# RP2040.net
KiCad netlist of a schematic drawn in Altium Designer
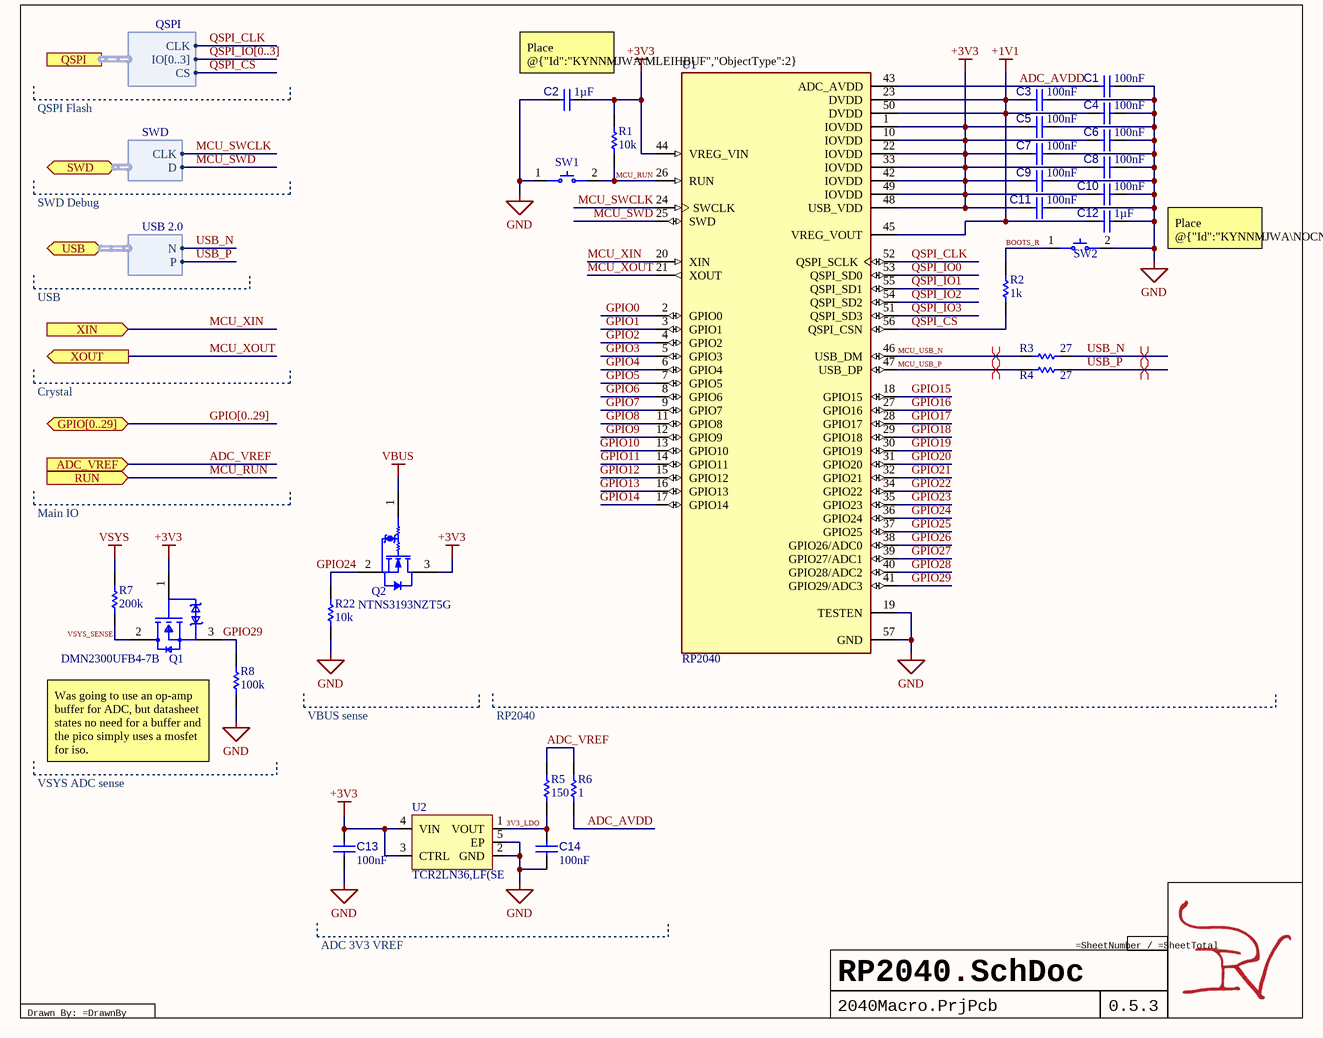
[diagram p0: RP2040.SchDoc]

(export (version "E")
  (design (tool "Eeschema 10.0.6"))
  (components
    (comp (ref "C1")
      (value "100nF")
      (footprint "CAP 0201_0603")
      (fields (field (name "Comment") "CL03A104KQ3NNNC"))
      (libsource (lib "IIT Motorsports") (part "CAP-NP-2"))
    )
    (comp (ref "C2")
      (value "1µF")
      (footprint "CAP 0201_0603")
      (fields (field (name "Comment") "GRM033R60J105MEA2D"))
      (libsource (lib "IIT Motorsports") (part "CAP-NP-2"))
    )
    (comp (ref "C3")
      (value "100nF")
      (footprint "CAP 0201_0603")
      (fields (field (name "Comment") "CL03A104KQ3NNNC"))
      (libsource (lib "IIT Motorsports") (part "CAP-NP-2"))
    )
    (comp (ref "C4")
      (value "100nF")
      (footprint "CAP 0201_0603")
      (fields (field (name "Comment") "CL03A104KQ3NNNC"))
      (libsource (lib "IIT Motorsports") (part "CAP-NP-2"))
    )
    (comp (ref "C5")
      (value "100nF")
      (footprint "CAP 0201_0603")
      (fields (field (name "Comment") "CL03A104KQ3NNNC"))
      (libsource (lib "IIT Motorsports") (part "CAP-NP-2"))
    )
    (comp (ref "C6")
      (value "100nF")
      (footprint "CAP 0201_0603")
      (fields (field (name "Comment") "CL03A104KQ3NNNC"))
      (libsource (lib "IIT Motorsports") (part "CAP-NP-2"))
    )
    (comp (ref "C7")
      (value "100nF")
      (footprint "CAP 0201_0603")
      (fields (field (name "Comment") "CL03A104KQ3NNNC"))
      (libsource (lib "IIT Motorsports") (part "CAP-NP-2"))
    )
    (comp (ref "C8")
      (value "100nF")
      (footprint "CAP 0201_0603")
      (fields (field (name "Comment") "CL03A104KQ3NNNC"))
      (libsource (lib "IIT Motorsports") (part "CAP-NP-2"))
    )
    (comp (ref "C9")
      (value "100nF")
      (footprint "CAP 0201_0603")
      (fields (field (name "Comment") "CL03A104KQ3NNNC"))
      (libsource (lib "IIT Motorsports") (part "CAP-NP-2"))
    )
    (comp (ref "C10")
      (value "100nF")
      (footprint "CAP 0201_0603")
      (fields (field (name "Comment") "CL03A104KQ3NNNC"))
      (libsource (lib "IIT Motorsports") (part "CAP-NP-2"))
    )
    (comp (ref "C11")
      (value "100nF")
      (footprint "CAP 0201_0603")
      (fields (field (name "Comment") "CL03A104KQ3NNNC"))
      (libsource (lib "IIT Motorsports") (part "CAP-NP-2"))
    )
    (comp (ref "C12")
      (value "1µF")
      (footprint "CAP 0201_0603")
      (fields (field (name "Comment") "GRM033R60J105MEA2D"))
      (libsource (lib "IIT Motorsports") (part "CAP-NP-2"))
    )
    (comp (ref "C13")
      (value "100nF")
      (footprint "CAP 0201_0603")
      (fields (field (name "Comment") "CL03A104KQ3NNNC"))
      (libsource (lib "IIT Motorsports") (part "CAP-NP-2"))
    )
    (comp (ref "C14")
      (value "100nF")
      (footprint "CAP 0201_0603")
      (fields (field (name "Comment") "CL03A104KQ3NNNC"))
      (libsource (lib "IIT Motorsports") (part "CAP-NP-2"))
    )
    (comp (ref "Q1")
      (value "DMN2300UFB4-7B")
      (footprint "FP-X2-DFN1006-3-MFG")
      (libsource (lib "IIT Motorsports") (part "a29196b179eec536a16aaf037fa858d"))
    )
    (comp (ref "Q2")
      (value "NTNS3193NZT5G")
      (footprint "ONSC-XLLGA-3-713AB_V")
      (libsource (lib "IIT Motorsports") (part "ONSC-NMOS-G1S2D3-3_I"))
    )
    (comp (ref "R1")
      (value "10k")
      (footprint "RES 0201_0603")
      (fields
        (field (name "POWER") "50mW")
        (field (name "TOLERANCE") "1%")
        (field (name "Comment") "10k-0201-0.05/1")
      )
      (libsource (lib "IIT Motorsports") (part "RES"))
    )
    (comp (ref "R2")
      (value "1k")
      (footprint "RES 0201_0603")
      (fields (field (name "POWER") "50mW") (field (name "TOLERANCE") "1%"))
      (libsource (lib "IIT Motorsports") (part "RES"))
    )
    (comp (ref "R3")
      (value "27")
      (footprint "RES 0201_0603")
      (fields
        (field (name "TOLERANCE") "1%")
        (field (name "POWER") "50mW")
        (field (name "Comment") "27-0201-0.05/1")
      )
      (libsource (lib "IIT Motorsports") (part "RES"))
    )
    (comp (ref "R4")
      (value "27")
      (footprint "RES 0201_0603")
      (fields
        (field (name "TOLERANCE") "1%")
        (field (name "POWER") "50mW")
        (field (name "Comment") "27-0201-0.05/1")
      )
      (libsource (lib "IIT Motorsports") (part "RES"))
    )
    (comp (ref "R5")
      (value "150")
      (footprint "RES 0201_0603")
      (fields
        (field (name "TOLERANCE") "1%")
        (field (name "POWER") "50mW")
        (field (name "Comment") "150-0201-0.05/1")
      )
      (libsource (lib "IIT Motorsports") (part "RES"))
    )
    (comp (ref "R6")
      (value "1")
      (footprint "RES 0201_0603")
      (fields
        (field (name "POWER") "50mW")
        (field (name "TOLERANCE") "1%")
        (field (name "Comment") "1-0201-0.05/1")
      )
      (libsource (lib "IIT Motorsports") (part "RES"))
    )
    (comp (ref "R7")
      (value "200k")
      (footprint "RES 0201_0603")
      (fields
        (field (name "TOLERANCE") "1%")
        (field (name "POWER") "50mW")
        (field (name "Comment") "200k-0201-0.05/1")
      )
      (libsource (lib "IIT Motorsports") (part "RES"))
    )
    (comp (ref "R8")
      (value "100k")
      (footprint "RES 0201_0603")
      (fields
        (field (name "TOLERANCE") "1%")
        (field (name "POWER") "50mW")
        (field (name "Comment") "100k-0201-0.05/1")
      )
      (libsource (lib "IIT Motorsports") (part "RES"))
    )
    (comp (ref "R22")
      (value "10k")
      (footprint "RES 0201_0603")
      (fields
        (field (name "POWER") "50mW")
        (field (name "TOLERANCE") "1%")
        (field (name "Comment") "10k-0201-0.05/1")
      )
      (libsource (lib "IIT Motorsports") (part "RES"))
    )
    (comp (ref "SW1")
      (value "EVP-BB2A9B000")
      (footprint "FP-EVP-BB2A9B000-MFG")
      (description "Switch Tactile N.O. SPST Round Button Gull Wing 0.02A 15VDC 1.6N SMD T/R")
      (libsource (lib "IIT Motorsports") (part "2dec56ad4e2c308d4a934808de6b739"))
    )
    (comp (ref "SW2")
      (value "LS38G2F-T")
      (footprint "LS38G2F-T-Footprint-1")
      (description "Top-press Tactile Switch")
      (libsource (lib "IIT Motorsports") (part "LS38G2F-T-Symbol-1"))
    )
    (comp (ref "U1")
      (value "RP2040")
      (footprint "QFN40P700X700X90-57N")
      (description "Mcu, 32 Bit, 133MHZ, QFN-56;")
      (fields (field (name "MF") "{'manufacturer': u'Raspberry Pi'}"))
      (libsource (lib "IIT Motorsports") (part "RP2040"))
    )
    (comp (ref "U2")
      (value "TCR2LN36,LF(SE")
      (footprint "SDFN4_TOS")
      (description "LDO Voltage Regulators LDO Reg Vout=3.6V I=200mA")
      (libsource (lib "IIT Motorsports") (part "TCR2LN36"))
    )
  )
  (nets
    (net (code "5") (name "+1V1") (class "Default")
      (node (ref "C12") (pin "1") (pinfunction "1_1") (pintype "passive"))
      (node (ref "C3") (pin "1") (pinfunction "1_1") (pintype "passive"))
      (node (ref "C4") (pin "1") (pinfunction "1_1") (pintype "passive"))
      (node (ref "U1") (pin "23") (pinfunction "DVDD_23") (pintype "power_in"))
      (node (ref "U1") (pin "45") (pinfunction "VREG_VOUT_45") (pintype "power_in"))
      (node (ref "U1") (pin "50") (pinfunction "DVDD_50") (pintype "power_in"))
    )
    (net (code "6") (name "+3V3") (class "Default")
      (node (ref "C10") (pin "1") (pinfunction "1_1") (pintype "passive"))
      (node (ref "C11") (pin "1") (pinfunction "1_1") (pintype "passive"))
      (node (ref "C13") (pin "2") (pinfunction "2_2") (pintype "passive"))
      (node (ref "C2") (pin "2") (pinfunction "2_2") (pintype "passive"))
      (node (ref "C5") (pin "1") (pinfunction "1_1") (pintype "passive"))
      (node (ref "C6") (pin "1") (pinfunction "1_1") (pintype "passive"))
      (node (ref "C7") (pin "1") (pinfunction "1_1") (pintype "passive"))
      (node (ref "C8") (pin "1") (pinfunction "1_1") (pintype "passive"))
      (node (ref "C9") (pin "1") (pinfunction "1_1") (pintype "passive"))
      (node (ref "Q1") (pin "1") (pinfunction "G_1") (pintype "passive"))
      (node (ref "Q2") (pin "3") (pinfunction "D_3") (pintype "passive"))
      (node (ref "R1") (pin "2") (pinfunction "2_2") (pintype "passive"))
      (node (ref "U1") (pin "1") (pinfunction "IOVDD_1") (pintype "power_in"))
      (node (ref "U1") (pin "10") (pinfunction "IOVDD_10") (pintype "power_in"))
      (node (ref "U1") (pin "22") (pinfunction "IOVDD_22") (pintype "power_in"))
      (node (ref "U1") (pin "33") (pinfunction "IOVDD_33") (pintype "power_in"))
      (node (ref "U1") (pin "42") (pinfunction "IOVDD_42") (pintype "power_in"))
      (node (ref "U1") (pin "44") (pinfunction "VREG_VIN_44") (pintype "input"))
      (node (ref "U1") (pin "48") (pinfunction "USB_VDD_48") (pintype "power_in"))
      (node (ref "U1") (pin "49") (pinfunction "IOVDD_49") (pintype "power_in"))
      (node (ref "U2") (pin "3") (pinfunction "CTRL_3") (pintype "passive"))
      (node (ref "U2") (pin "4") (pinfunction "VIN_4") (pintype "passive"))
    )
    (net (code "7") (name "/3V3_LDO") (class "Default")
      (node (ref "C14") (pin "2") (pinfunction "2_2") (pintype "passive"))
      (node (ref "R5") (pin "1") (pinfunction "1_1") (pintype "passive"))
      (node (ref "U2") (pin "1") (pinfunction "VOUT_1") (pintype "passive"))
    )
    (net (code "8") (name "/ADC_AVDD") (class "Default")
      (node (ref "C1") (pin "1") (pinfunction "1_1") (pintype "passive"))
      (node (ref "R6") (pin "1") (pinfunction "1_1") (pintype "passive"))
      (node (ref "U1") (pin "43") (pinfunction "ADC_AVDD_43") (pintype "power_in"))
    )
    (net (code "9") (name "/ADC_VREF") (class "Default")
      (node (ref "R5") (pin "2") (pinfunction "2_2") (pintype "passive"))
      (node (ref "R6") (pin "2") (pinfunction "2_2") (pintype "passive"))
    )
    (net (code "10") (name "/BOOTS_R") (class "Default")
      (node (ref "R2") (pin "1") (pinfunction "1_1") (pintype "passive"))
      (node (ref "SW2") (pin "1") (pinfunction "1_1") (pintype "passive"))
    )
    (net (code "11") (name "/GPIO0") (class "Default")
      (node (ref "U1") (pin "2") (pinfunction "GPIO0_2") (pintype "bidirectional"))
    )
    (net (code "12") (name "/GPIO1") (class "Default")
      (node (ref "U1") (pin "3") (pinfunction "GPIO1_3") (pintype "bidirectional"))
    )
    (net (code "13") (name "/GPIO2") (class "Default")
      (node (ref "U1") (pin "4") (pinfunction "GPIO2_4") (pintype "bidirectional"))
    )
    (net (code "14") (name "/GPIO3") (class "Default")
      (node (ref "U1") (pin "5") (pinfunction "GPIO3_5") (pintype "bidirectional"))
    )
    (net (code "15") (name "/GPIO4") (class "Default")
      (node (ref "U1") (pin "6") (pinfunction "GPIO4_6") (pintype "bidirectional"))
    )
    (net (code "16") (name "/GPIO5") (class "Default")
      (node (ref "U1") (pin "7") (pinfunction "GPIO5_7") (pintype "bidirectional"))
    )
    (net (code "17") (name "/GPIO6") (class "Default")
      (node (ref "U1") (pin "8") (pinfunction "GPIO6_8") (pintype "bidirectional"))
    )
    (net (code "18") (name "/GPIO7") (class "Default")
      (node (ref "U1") (pin "9") (pinfunction "GPIO7_9") (pintype "bidirectional"))
    )
    (net (code "19") (name "/GPIO8") (class "Default")
      (node (ref "U1") (pin "11") (pinfunction "GPIO8_11") (pintype "bidirectional"))
    )
    (net (code "20") (name "/GPIO9") (class "Default")
      (node (ref "U1") (pin "12") (pinfunction "GPIO9_12") (pintype "bidirectional"))
    )
    (net (code "21") (name "/GPIO10") (class "Default")
      (node (ref "U1") (pin "13") (pinfunction "GPIO10_13") (pintype "bidirectional"))
    )
    (net (code "22") (name "/GPIO11") (class "Default")
      (node (ref "U1") (pin "14") (pinfunction "GPIO11_14") (pintype "bidirectional"))
    )
    (net (code "23") (name "/GPIO12") (class "Default")
      (node (ref "U1") (pin "15") (pinfunction "GPIO12_15") (pintype "bidirectional"))
    )
    (net (code "24") (name "/GPIO13") (class "Default")
      (node (ref "U1") (pin "16") (pinfunction "GPIO13_16") (pintype "bidirectional"))
    )
    (net (code "25") (name "/GPIO14") (class "Default")
      (node (ref "U1") (pin "17") (pinfunction "GPIO14_17") (pintype "bidirectional"))
    )
    (net (code "26") (name "/GPIO15") (class "Default")
      (node (ref "U1") (pin "18") (pinfunction "GPIO15_18") (pintype "bidirectional"))
    )
    (net (code "27") (name "/GPIO16") (class "Default")
      (node (ref "U1") (pin "27") (pinfunction "GPIO16_27") (pintype "bidirectional"))
    )
    (net (code "28") (name "/GPIO17") (class "Default")
      (node (ref "U1") (pin "28") (pinfunction "GPIO17_28") (pintype "bidirectional"))
    )
    (net (code "29") (name "/GPIO18") (class "Default")
      (node (ref "U1") (pin "29") (pinfunction "GPIO18_29") (pintype "bidirectional"))
    )
    (net (code "30") (name "/GPIO19") (class "Default")
      (node (ref "U1") (pin "30") (pinfunction "GPIO19_30") (pintype "bidirectional"))
    )
    (net (code "31") (name "/GPIO20") (class "Default")
      (node (ref "U1") (pin "31") (pinfunction "GPIO20_31") (pintype "bidirectional"))
    )
    (net (code "32") (name "/GPIO21") (class "Default")
      (node (ref "U1") (pin "32") (pinfunction "GPIO21_32") (pintype "bidirectional"))
    )
    (net (code "33") (name "/GPIO22") (class "Default")
      (node (ref "U1") (pin "34") (pinfunction "GPIO22_34") (pintype "bidirectional"))
    )
    (net (code "34") (name "/GPIO23") (class "Default")
      (node (ref "U1") (pin "35") (pinfunction "GPIO23_35") (pintype "bidirectional"))
    )
    (net (code "35") (name "/GPIO24") (class "Default")
      (node (ref "Q2") (pin "2") (pinfunction "S_2") (pintype "passive"))
      (node (ref "R22") (pin "2") (pinfunction "2_2") (pintype "passive"))
      (node (ref "U1") (pin "36") (pinfunction "GPIO24_36") (pintype "bidirectional"))
    )
    (net (code "36") (name "/GPIO25") (class "Default")
      (node (ref "U1") (pin "37") (pinfunction "GPIO25_37") (pintype "bidirectional"))
    )
    (net (code "37") (name "/GPIO26") (class "Default")
      (node (ref "U1") (pin "38") (pinfunction "GPIO26/ADC0_38") (pintype "bidirectional"))
    )
    (net (code "38") (name "/GPIO27") (class "Default")
      (node (ref "U1") (pin "39") (pinfunction "GPIO27/ADC1_39") (pintype "bidirectional"))
    )
    (net (code "39") (name "/GPIO28") (class "Default")
      (node (ref "U1") (pin "40") (pinfunction "GPIO28/ADC2_40") (pintype "bidirectional"))
    )
    (net (code "40") (name "/GPIO29") (class "Default")
      (node (ref "Q1") (pin "3") (pinfunction "S_3") (pintype "passive"))
      (node (ref "R8") (pin "2") (pinfunction "2_2") (pintype "passive"))
      (node (ref "U1") (pin "41") (pinfunction "GPIO29/ADC3_41") (pintype "bidirectional"))
    )
    (net (code "42") (name "/MCU_RUN") (class "Default")
      (node (ref "R1") (pin "1") (pinfunction "1_1") (pintype "passive"))
      (node (ref "SW1") (pin "2") (pinfunction "2_2") (pintype "passive"))
      (node (ref "U1") (pin "26") (pinfunction "RUN_26") (pintype "input"))
    )
    (net (code "43") (name "/MCU_SWCLK") (class "Default")
      (node (ref "U1") (pin "24") (pinfunction "SWCLK_24") (pintype "input"))
    )
    (net (code "44") (name "/MCU_SWD") (class "Default")
      (node (ref "U1") (pin "25") (pinfunction "SWD_25") (pintype "bidirectional"))
    )
    (net (code "45") (name "/MCU_USB_N") (class "Default")
      (node (ref "R3") (pin "1") (pinfunction "1_1") (pintype "passive"))
      (node (ref "U1") (pin "46") (pinfunction "USB_DM_46") (pintype "bidirectional"))
    )
    (net (code "46") (name "/MCU_USB_P") (class "Default")
      (node (ref "R4") (pin "1") (pinfunction "1_1") (pintype "passive"))
      (node (ref "U1") (pin "47") (pinfunction "USB_DP_47") (pintype "bidirectional"))
    )
    (net (code "47") (name "/MCU_XIN") (class "Default")
      (node (ref "U1") (pin "20") (pinfunction "XIN_20") (pintype "input"))
    )
    (net (code "48") (name "/MCU_XOUT") (class "Default")
      (node (ref "U1") (pin "21") (pinfunction "XOUT_21") (pintype "output"))
    )
    (net (code "49") (name "/QSPI_CLK") (class "Default")
      (node (ref "U1") (pin "52") (pinfunction "QSPI_SCLK_52") (pintype "bidirectional"))
    )
    (net (code "50") (name "/QSPI_CS") (class "Default")
      (node (ref "R2") (pin "2") (pinfunction "2_2") (pintype "passive"))
      (node (ref "U1") (pin "56") (pinfunction "QSPI_CSN_56") (pintype "bidirectional"))
    )
    (net (code "51") (name "/QSPI_IO0") (class "Default")
      (node (ref "U1") (pin "53") (pinfunction "QSPI_SD0_53") (pintype "bidirectional"))
    )
    (net (code "52") (name "/QSPI_IO1") (class "Default")
      (node (ref "U1") (pin "55") (pinfunction "QSPI_SD1_55") (pintype "bidirectional"))
    )
    (net (code "53") (name "/QSPI_IO2") (class "Default")
      (node (ref "U1") (pin "54") (pinfunction "QSPI_SD2_54") (pintype "bidirectional"))
    )
    (net (code "54") (name "/QSPI_IO3") (class "Default")
      (node (ref "U1") (pin "51") (pinfunction "QSPI_SD3_51") (pintype "bidirectional"))
    )
    (net (code "56") (name "/USB_N") (class "Default")
      (node (ref "R3") (pin "2") (pinfunction "2_2") (pintype "passive"))
    )
    (net (code "57") (name "/USB_P") (class "Default")
      (node (ref "R4") (pin "2") (pinfunction "2_2") (pintype "passive"))
    )
    (net (code "58") (name "/VSYS_SENSE") (class "Default")
      (node (ref "Q1") (pin "2") (pinfunction "D_2") (pintype "passive"))
      (node (ref "R7") (pin "1") (pinfunction "1_1") (pintype "passive"))
    )
    (net (code "62") (name "GND") (class "Default")
      (node (ref "C1") (pin "2") (pinfunction "2_2") (pintype "passive"))
      (node (ref "C10") (pin "2") (pinfunction "2_2") (pintype "passive"))
      (node (ref "C11") (pin "2") (pinfunction "2_2") (pintype "passive"))
      (node (ref "C12") (pin "2") (pinfunction "2_2") (pintype "passive"))
      (node (ref "C13") (pin "1") (pinfunction "1_1") (pintype "passive"))
      (node (ref "C14") (pin "1") (pinfunction "1_1") (pintype "passive"))
      (node (ref "C2") (pin "1") (pinfunction "1_1") (pintype "passive"))
      (node (ref "C3") (pin "2") (pinfunction "2_2") (pintype "passive"))
      (node (ref "C4") (pin "2") (pinfunction "2_2") (pintype "passive"))
      (node (ref "C5") (pin "2") (pinfunction "2_2") (pintype "passive"))
      (node (ref "C6") (pin "2") (pinfunction "2_2") (pintype "passive"))
      (node (ref "C7") (pin "2") (pinfunction "2_2") (pintype "passive"))
      (node (ref "C8") (pin "2") (pinfunction "2_2") (pintype "passive"))
      (node (ref "C9") (pin "2") (pinfunction "2_2") (pintype "passive"))
      (node (ref "R22") (pin "1") (pinfunction "1_1") (pintype "passive"))
      (node (ref "R8") (pin "1") (pinfunction "1_1") (pintype "passive"))
      (node (ref "SW1") (pin "1") (pinfunction "1_1") (pintype "passive"))
      (node (ref "SW2") (pin "2") (pinfunction "2_2") (pintype "passive"))
      (node (ref "U1") (pin "19") (pinfunction "TESTEN_19") (pintype "passive"))
      (node (ref "U1") (pin "57") (pinfunction "GND_57") (pintype "power_in"))
      (node (ref "U2") (pin "2") (pinfunction "GND_2") (pintype "passive"))
      (node (ref "U2") (pin "5") (pinfunction "EP_5") (pintype "passive"))
    )
    (net (code "63") (name "VBUS") (class "Default")
      (node (ref "Q2") (pin "1") (pinfunction "G_1") (pintype "passive"))
    )
    (net (code "64") (name "VSYS") (class "Default")
      (node (ref "R7") (pin "2") (pinfunction "2_2") (pintype "passive"))
    )
  )
)
